# 8_imu_debug_conn.net
KiCad netlist of a schematic drawn in Altium Designer
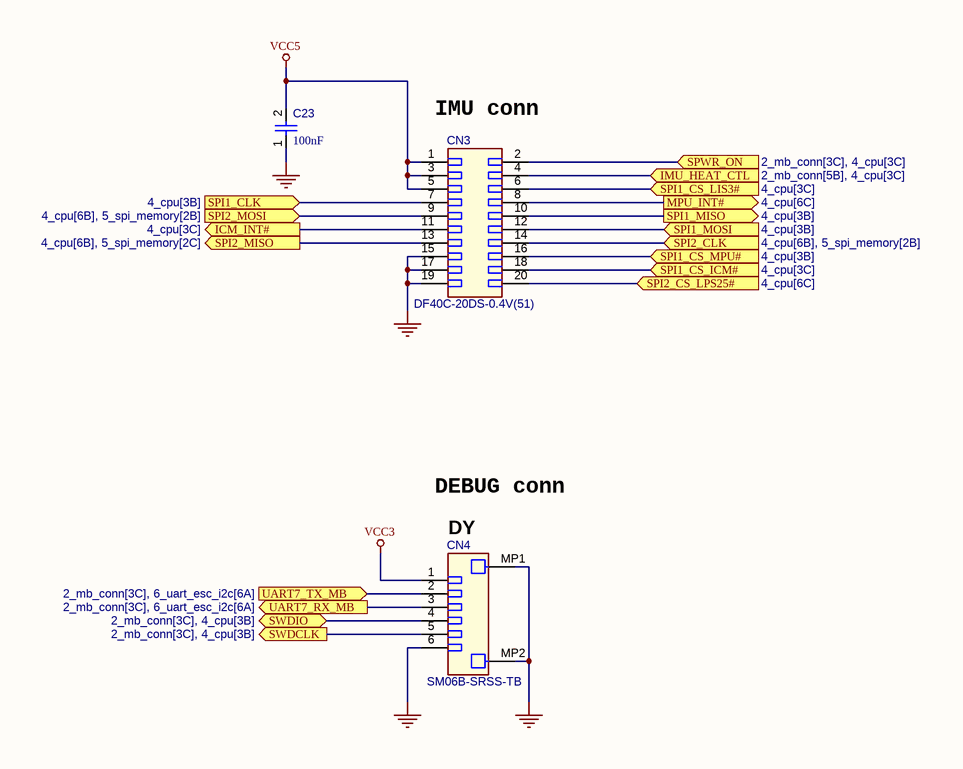
[diagram p0: 8_imu&debug_conn.SchDoc]

(export (version "E")
  (design (tool "Eeschema 10.0.6"))
  (components
    (comp (ref "C23")
      (value "100nF")
      (footprint "CAPC0402(1005)60_L")
      (description "Chip Capacitor, 100nF +/-20%, 10V, 0402, Thickness 0.6 mm")
      (fields (field (name "TOLERANCE") "20%") (field (name "Comment") "Capacitor 100nF +/-20% 10V 0402"))
      (libsource (lib "SKA- Automa玢o de Engenharias") (part "CAP-NP-2"))
    )
    (comp (ref "CN3")
      (value "DF40C-20DS-0.4V(51)")
      (footprint "HIRO-DF40C-20DS-0.4V(51)_V")
      (description "Receptacle Connector, 30 V, 0.3 A, -35 to 85 degC, RoHS, Tape and Reel")
      (fields (field (name "PART NUMBER") "DF40C"))
      (libsource (lib "SKA- Automa玢o de Engenharias") (part "CMP-00114-7"))
    )
    (comp (ref "CN4")
      (value "SM06B-SRSS-TB")
      (footprint "JST-SM06B-SRSS-TB_V")
      (description "Male Header, Pitch 1 mm, 1 x 6 Position, Height 2.95 mm, -25 to 85 degC, RoHS, Tape and Reel")
      (fields (field (name "PART NUMBER") "SM06B"))
      (libsource (lib "SKA- Automa玢o de Engenharias") (part "CMP-00143-5"))
    )
  )
  (nets
    (net (code "1") (name "/ICM_INT#") (class "Default")
      (node (ref "CN3") (pin "11") (pinfunction "11_11") (pintype "passive"))
    )
    (net (code "2") (name "/IMU_HEAT_CTL") (class "Default")
      (node (ref "CN3") (pin "4") (pinfunction "4_4") (pintype "passive"))
    )
    (net (code "3") (name "/MPU_INT#") (class "Default")
      (node (ref "CN3") (pin "8") (pinfunction "8_8") (pintype "passive"))
    )
    (net (code "4") (name "/SPI1_CLK") (class "Default")
      (node (ref "CN3") (pin "7") (pinfunction "7_7") (pintype "passive"))
    )
    (net (code "5") (name "/SPI1_CS_ICM#") (class "Default")
      (node (ref "CN3") (pin "18") (pinfunction "18_18") (pintype "passive"))
    )
    (net (code "6") (name "/SPI1_CS_LIS3#") (class "Default")
      (node (ref "CN3") (pin "6") (pinfunction "6_6") (pintype "passive"))
    )
    (net (code "7") (name "/SPI1_CS_MPU#") (class "Default")
      (node (ref "CN3") (pin "16") (pinfunction "16_16") (pintype "passive"))
    )
    (net (code "8") (name "/SPI1_MISO") (class "Default")
      (node (ref "CN3") (pin "10") (pinfunction "10_10") (pintype "passive"))
    )
    (net (code "9") (name "/SPI1_MOSI") (class "Default")
      (node (ref "CN3") (pin "12") (pinfunction "12_12") (pintype "passive"))
    )
    (net (code "10") (name "/SPI2_CLK") (class "Default")
      (node (ref "CN3") (pin "14") (pinfunction "14_14") (pintype "passive"))
    )
    (net (code "11") (name "/SPI2_CS_LPS25#") (class "Default")
      (node (ref "CN3") (pin "20") (pinfunction "20_20") (pintype "passive"))
    )
    (net (code "12") (name "/SPI2_MISO") (class "Default")
      (node (ref "CN3") (pin "13") (pinfunction "13_13") (pintype "passive"))
    )
    (net (code "13") (name "/SPI2_MOSI") (class "Default")
      (node (ref "CN3") (pin "9") (pinfunction "9_9") (pintype "passive"))
    )
    (net (code "14") (name "/SPWR_ON") (class "Default")
      (node (ref "CN3") (pin "2") (pinfunction "2_2") (pintype "passive"))
    )
    (net (code "15") (name "/SWDCLK") (class "Default")
      (node (ref "CN4") (pin "5") (pinfunction "5_5") (pintype "passive"))
    )
    (net (code "16") (name "/SWDIO") (class "Default")
      (node (ref "CN4") (pin "4") (pinfunction "4_4") (pintype "passive"))
    )
    (net (code "17") (name "/UART7_RX_MB") (class "Default")
      (node (ref "CN4") (pin "3") (pinfunction "3_3") (pintype "passive"))
    )
    (net (code "18") (name "/UART7_TX_MB") (class "Default")
      (node (ref "CN4") (pin "2") (pinfunction "2_2") (pintype "passive"))
    )
    (net (code "19") (name "GND") (class "Default")
      (node (ref "C23") (pin "1") (pinfunction "1_1") (pintype "passive"))
      (node (ref "CN3") (pin "15") (pinfunction "15_15") (pintype "passive"))
      (node (ref "CN3") (pin "17") (pinfunction "17_17") (pintype "passive"))
      (node (ref "CN3") (pin "19") (pinfunction "19_19") (pintype "passive"))
      (node (ref "CN4") (pin "6") (pinfunction "6_6") (pintype "passive"))
      (node (ref "CN4") (pin "MP1") (pinfunction "MP1_MP1") (pintype "passive"))
      (node (ref "CN4") (pin "MP2") (pinfunction "MP2_MP2") (pintype "passive"))
    )
    (net (code "20") (name "VCC3") (class "Default")
      (node (ref "CN4") (pin "1") (pinfunction "1_1") (pintype "passive"))
    )
    (net (code "21") (name "VCC5") (class "Default")
      (node (ref "C23") (pin "2") (pinfunction "2_2") (pintype "passive"))
      (node (ref "CN3") (pin "1") (pinfunction "1_1") (pintype "passive"))
      (node (ref "CN3") (pin "3") (pinfunction "3_3") (pintype "passive"))
      (node (ref "CN3") (pin "5") (pinfunction "5_5") (pintype "passive"))
    )
  )
)
